# FPGA_SLM.net
KiCad netlist of a schematic drawn in Altium Designer
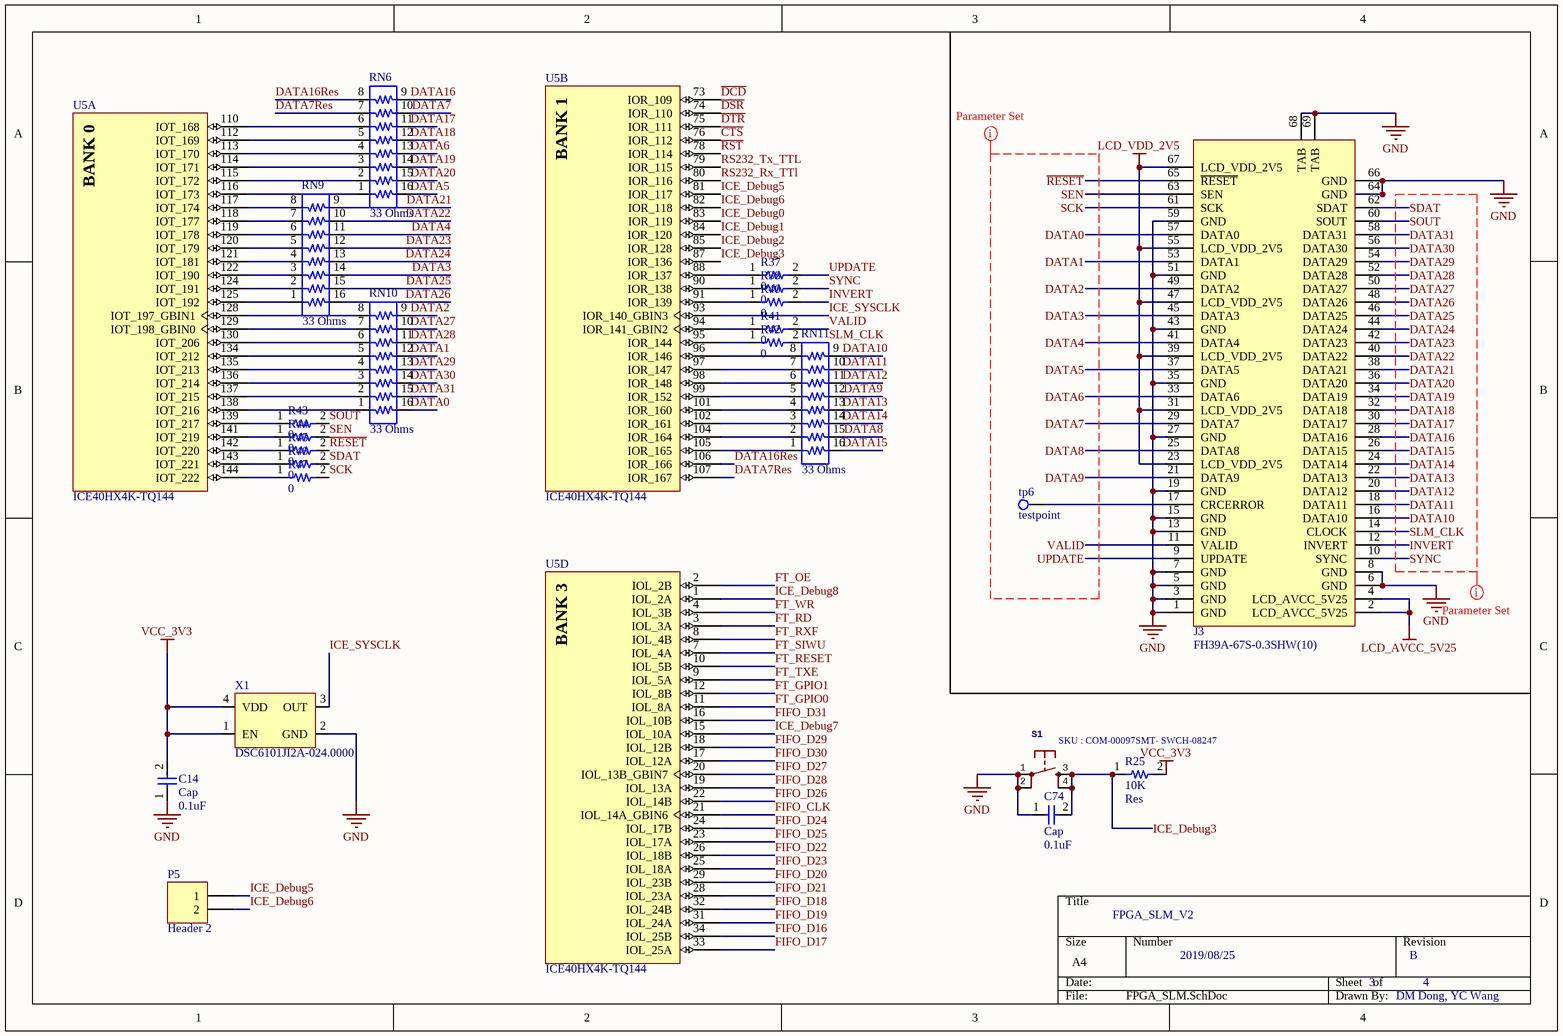
[diagram p0: FPGA_SLM.SchDoc]

(export (version "E")
  (design (tool "Eeschema 10.0.6"))
  (components
    (comp (ref "C14")
      (value "0.1uF")
      (footprint "Cap_0.1uF")
      (description "Multilayer Ceramic Capacitors MLCC - SMD/SMT 0.1uF 10% 50V AEC-Q200")
      (fields
        (field (name "COMPONENT NAME") "Cap")
        (field (name "Comment") "AC0603KRX7R9BB104")
        (field (name "CREATED BY") "Daoming Dong")
      )
      (libsource (lib "USB_FPGA_SLM_v1") (part "Cap_0.1uF"))
    )
    (comp (ref "C74")
      (value "0.1uF")
      (footprint "Cap_0.1uF")
      (description "Multilayer Ceramic Capacitors MLCC - SMD/SMT 0.1uF 10% 50V AEC-Q200")
      (fields
        (field (name "COMPONENT NAME") "Cap")
        (field (name "Comment") "AC0603KRX7R9BB104")
        (field (name "CREATED BY") "Daoming Dong")
      )
      (libsource (lib "USB_FPGA_SLM_v1") (part "Cap_0.1uF"))
    )
    (comp (ref "J3")
      (value "FH39A-67S-0.3SHW(10)")
      (footprint "Hirose_connector")
      (description "FFC & FPC Connectors FPC ZIF CONN 67 POS SMT HORZ MNT")
      (fields (field (name "CREATED BY") "Daoming Dong"))
      (libsource (lib "USB_FPGA_SLM_v1") (part "FH39A-67S-0.3SHW(10)"))
    )
    (comp (ref "P5")
      (value "Header 2")
      (footprint "HDR1X2")
      (description "Header, 2-Pin")
      (fields (field (name "PUBLISHER") "Altium Limited"))
      (libsource (lib "Miscellaneous Connectors") (part "Header 2"))
    )
    (comp (ref "R25")
      (value "10K")
      (footprint "RES_10K")
      (description "Thin Film Resistors - SMD 10K ohm 0.05% 50 ppm High-Precision")
      (fields
        (field (name "COMPONENT NAME") "Res")
        (field (name "Comment") "RT0603WRE0710KL")
        (field (name "CREATED BY") "Daoming Dong")
      )
      (libsource (lib "USB_FPGA_SLM_v1") (part "Res_10K"))
    )
    (comp (ref "R37")
      (value "0")
      (footprint "RES_0")
      (description "Thick Film Resistors - SMD 1/10Watt 0ohms Commercial Use")
      (fields (field (name "Comment") "CRCW06030000Z0EAC") (field (name "CREATED BY") "Daoming Dong"))
      (libsource (lib "USB_FPGA_SLM_v1") (part "Res_0"))
    )
    (comp (ref "R38")
      (value "0")
      (footprint "RES_0")
      (description "Thick Film Resistors - SMD 1/10Watt 0ohms Commercial Use")
      (fields (field (name "Comment") "CRCW06030000Z0EAC") (field (name "CREATED BY") "Daoming Dong"))
      (libsource (lib "USB_FPGA_SLM_v1") (part "Res_0"))
    )
    (comp (ref "R40")
      (value "0")
      (footprint "RES_0")
      (description "Thick Film Resistors - SMD 1/10Watt 0ohms Commercial Use")
      (fields (field (name "Comment") "CRCW06030000Z0EAC") (field (name "CREATED BY") "Daoming Dong"))
      (libsource (lib "USB_FPGA_SLM_v1") (part "Res_0"))
    )
    (comp (ref "R41")
      (value "0")
      (footprint "RES_0")
      (description "Thick Film Resistors - SMD 1/10Watt 0ohms Commercial Use")
      (fields (field (name "Comment") "CRCW06030000Z0EAC") (field (name "CREATED BY") "Daoming Dong"))
      (libsource (lib "USB_FPGA_SLM_v1") (part "Res_0"))
    )
    (comp (ref "R42")
      (value "0")
      (footprint "RES_0")
      (description "Thick Film Resistors - SMD 1/10Watt 0ohms Commercial Use")
      (fields (field (name "Comment") "CRCW06030000Z0EAC") (field (name "CREATED BY") "Daoming Dong"))
      (libsource (lib "USB_FPGA_SLM_v1") (part "Res_0"))
    )
    (comp (ref "R43")
      (value "0")
      (footprint "RES_0")
      (description "Thick Film Resistors - SMD 1/10Watt 0ohms Commercial Use")
      (fields (field (name "Comment") "CRCW06030000Z0EAC") (field (name "CREATED BY") "Daoming Dong"))
      (libsource (lib "USB_FPGA_SLM_v1") (part "Res_0"))
    )
    (comp (ref "R44")
      (value "0")
      (footprint "RES_0")
      (description "Thick Film Resistors - SMD 1/10Watt 0ohms Commercial Use")
      (fields (field (name "Comment") "CRCW06030000Z0EAC") (field (name "CREATED BY") "Daoming Dong"))
      (libsource (lib "USB_FPGA_SLM_v1") (part "Res_0"))
    )
    (comp (ref "R45")
      (value "0")
      (footprint "RES_0")
      (description "Thick Film Resistors - SMD 1/10Watt 0ohms Commercial Use")
      (fields (field (name "Comment") "CRCW06030000Z0EAC") (field (name "CREATED BY") "Daoming Dong"))
      (libsource (lib "USB_FPGA_SLM_v1") (part "Res_0"))
    )
    (comp (ref "R46")
      (value "0")
      (footprint "RES_0")
      (description "Thick Film Resistors - SMD 1/10Watt 0ohms Commercial Use")
      (fields (field (name "Comment") "CRCW06030000Z0EAC") (field (name "CREATED BY") "Daoming Dong"))
      (libsource (lib "USB_FPGA_SLM_v1") (part "Res_0"))
    )
    (comp (ref "R47")
      (value "0")
      (footprint "RES_0")
      (description "Thick Film Resistors - SMD 1/10Watt 0ohms Commercial Use")
      (fields (field (name "Comment") "CRCW06030000Z0EAC") (field (name "CREATED BY") "Daoming Dong"))
      (libsource (lib "USB_FPGA_SLM_v1") (part "Res_0"))
    )
    (comp (ref "RN6")
      (value "33 Ohms")
      (footprint "ResArray_0")
      (description "Resistor Networks & Arrays 33 OHM 5%")
      (fields (field (name "Comment") "EXB-2HV330JV"))
      (libsource (lib "USB_FPGA_SLM_v1") (part "ResArray"))
    )
    (comp (ref "RN9")
      (value "33 Ohms")
      (footprint "ResArray_0")
      (description "Resistor Networks & Arrays 33 OHM 5%")
      (fields (field (name "Comment") "EXB-2HV330JV"))
      (libsource (lib "USB_FPGA_SLM_v1") (part "ResArray"))
    )
    (comp (ref "RN10")
      (value "33 Ohms")
      (footprint "ResArray_0")
      (description "Resistor Networks & Arrays 33 OHM 5%")
      (fields (field (name "Comment") "EXB-2HV330JV"))
      (libsource (lib "USB_FPGA_SLM_v1") (part "ResArray"))
    )
    (comp (ref "RN11")
      (value "33 Ohms")
      (footprint "ResArray_0")
      (description "Resistor Networks & Arrays 33 OHM 5%")
      (fields (field (name "Comment") "EXB-2HV330JV"))
      (libsource (lib "USB_FPGA_SLM_v1") (part "ResArray"))
    )
    (comp (ref "S1")
      (value "SKU : COM-00097SMT- SWCH-08247")
      (footprint "TACTILE-PTH")
      (libsource (lib "SparkFun-Electromechanical") (part "TAC_SWITCHPTH"))
    )
    (comp (ref "tp6")
      (value "testpoint")
      (footprint "testpoint")
      (description "Testpoint for testing voltage")
      (fields (field (name "CREATED BY") "Daoming Dong"))
      (libsource (lib "USB_FPGA_SLM_v1") (part "Testpoint"))
    )
    (comp (ref "U5")
      (value "ICE40HX4K-TQ144")
      (footprint "LATC-TQFP-144_L")
      (fields (field (name "MANUFACTURER") "Lattice Semiconductor"))
      (libsource (lib "Lattice iCE40") (part "ICE40HX4K-TQ144"))
    )
    (comp (ref "X1")
      (value "DSC6101JI2A-024.0000")
      (footprint "24MHzOscillator")
      (description "Standard Clock Oscillators MEMS Oscillator, Ultra Low Power, LVCMOS, -40C-85C, 25ppm, 2.5x2.0mm")
      (fields (field (name "CREATED BY") "Daoming Dong"))
      (libsource (lib "USB_FPGA_SLM_v1") (part "24MHzOscillator"))
    )
  )
  (nets
    (net (code "1") (name "/DATA0") (class "Default")
      (node (ref "J3") (pin "57") (pinfunction "DATA0_57") (pintype "passive"))
      (node (ref "RN10") (pin "16") (pinfunction "16_16") (pintype "passive"))
    )
    (net (code "2") (name "/DATA1") (class "Default")
      (node (ref "J3") (pin "53") (pinfunction "DATA1_53") (pintype "passive"))
      (node (ref "RN10") (pin "12") (pinfunction "12_12") (pintype "passive"))
    )
    (net (code "3") (name "/DATA2") (class "Default")
      (node (ref "J3") (pin "49") (pinfunction "DATA2_49") (pintype "passive"))
      (node (ref "RN10") (pin "9") (pinfunction "9_9") (pintype "passive"))
    )
    (net (code "4") (name "/DATA3") (class "Default")
      (node (ref "J3") (pin "45") (pinfunction "DATA3_45") (pintype "passive"))
      (node (ref "RN9") (pin "14") (pinfunction "14_14") (pintype "passive"))
    )
    (net (code "5") (name "/DATA4") (class "Default")
      (node (ref "J3") (pin "41") (pinfunction "DATA4_41") (pintype "passive"))
      (node (ref "RN9") (pin "11") (pinfunction "11_11") (pintype "passive"))
    )
    (net (code "6") (name "/DATA5") (class "Default")
      (node (ref "J3") (pin "37") (pinfunction "DATA5_37") (pintype "passive"))
      (node (ref "RN6") (pin "16") (pinfunction "16_16") (pintype "passive"))
    )
    (net (code "7") (name "/DATA6") (class "Default")
      (node (ref "J3") (pin "33") (pinfunction "DATA6_33") (pintype "passive"))
      (node (ref "RN6") (pin "13") (pinfunction "13_13") (pintype "passive"))
    )
    (net (code "8") (name "/DATA7") (class "Default")
      (node (ref "J3") (pin "29") (pinfunction "DATA7_29") (pintype "passive"))
      (node (ref "RN6") (pin "10") (pinfunction "10_10") (pintype "passive"))
    )
    (net (code "9") (name "/DATA7Res") (class "Default")
      (node (ref "RN6") (pin "7") (pinfunction "7_7") (pintype "passive"))
      (node (ref "U5") (pin "107") (pinfunction "IOR_167_107") (pintype "bidirectional"))
    )
    (net (code "10") (name "/DATA8") (class "Default")
      (node (ref "J3") (pin "25") (pinfunction "DATA8_25") (pintype "passive"))
      (node (ref "RN11") (pin "15") (pinfunction "15_15") (pintype "passive"))
    )
    (net (code "11") (name "/DATA9") (class "Default")
      (node (ref "J3") (pin "21") (pinfunction "DATA9_21") (pintype "passive"))
      (node (ref "RN11") (pin "12") (pinfunction "12_12") (pintype "passive"))
    )
    (net (code "12") (name "/DATA10") (class "Default")
      (node (ref "J3") (pin "16") (pinfunction "DATA10_16") (pintype "passive"))
      (node (ref "RN11") (pin "9") (pinfunction "9_9") (pintype "passive"))
    )
    (net (code "13") (name "/DATA11") (class "Default")
      (node (ref "J3") (pin "18") (pinfunction "DATA11_18") (pintype "passive"))
      (node (ref "RN11") (pin "10") (pinfunction "10_10") (pintype "passive"))
    )
    (net (code "14") (name "/DATA12") (class "Default")
      (node (ref "J3") (pin "20") (pinfunction "DATA12_20") (pintype "passive"))
      (node (ref "RN11") (pin "11") (pinfunction "11_11") (pintype "passive"))
    )
    (net (code "15") (name "/DATA13") (class "Default")
      (node (ref "J3") (pin "22") (pinfunction "DATA13_22") (pintype "passive"))
      (node (ref "RN11") (pin "13") (pinfunction "13_13") (pintype "passive"))
    )
    (net (code "16") (name "/DATA14") (class "Default")
      (node (ref "J3") (pin "24") (pinfunction "DATA14_24") (pintype "passive"))
      (node (ref "RN11") (pin "14") (pinfunction "14_14") (pintype "passive"))
    )
    (net (code "17") (name "/DATA15") (class "Default")
      (node (ref "J3") (pin "26") (pinfunction "DATA15_26") (pintype "passive"))
      (node (ref "RN11") (pin "16") (pinfunction "16_16") (pintype "passive"))
    )
    (net (code "18") (name "/DATA16") (class "Default")
      (node (ref "J3") (pin "28") (pinfunction "DATA16_28") (pintype "passive"))
      (node (ref "RN6") (pin "9") (pinfunction "9_9") (pintype "passive"))
    )
    (net (code "19") (name "/DATA16Res") (class "Default")
      (node (ref "RN6") (pin "8") (pinfunction "8_8") (pintype "passive"))
      (node (ref "U5") (pin "106") (pinfunction "IOR_166_106") (pintype "bidirectional"))
    )
    (net (code "20") (name "/DATA17") (class "Default")
      (node (ref "J3") (pin "30") (pinfunction "DATA17_30") (pintype "passive"))
      (node (ref "RN6") (pin "11") (pinfunction "11_11") (pintype "passive"))
    )
    (net (code "21") (name "/DATA18") (class "Default")
      (node (ref "J3") (pin "32") (pinfunction "DATA18_32") (pintype "passive"))
      (node (ref "RN6") (pin "12") (pinfunction "12_12") (pintype "passive"))
    )
    (net (code "22") (name "/DATA19") (class "Default")
      (node (ref "J3") (pin "34") (pinfunction "DATA19_34") (pintype "passive"))
      (node (ref "RN6") (pin "14") (pinfunction "14_14") (pintype "passive"))
    )
    (net (code "23") (name "/DATA20") (class "Default")
      (node (ref "J3") (pin "36") (pinfunction "DATA20_36") (pintype "passive"))
      (node (ref "RN6") (pin "15") (pinfunction "15_15") (pintype "passive"))
    )
    (net (code "24") (name "/DATA21") (class "Default")
      (node (ref "J3") (pin "38") (pinfunction "DATA21_38") (pintype "passive"))
      (node (ref "RN9") (pin "9") (pinfunction "9_9") (pintype "passive"))
    )
    (net (code "25") (name "/DATA22") (class "Default")
      (node (ref "J3") (pin "40") (pinfunction "DATA22_40") (pintype "passive"))
      (node (ref "RN9") (pin "10") (pinfunction "10_10") (pintype "passive"))
    )
    (net (code "26") (name "/DATA23") (class "Default")
      (node (ref "J3") (pin "42") (pinfunction "DATA23_42") (pintype "passive"))
      (node (ref "RN9") (pin "12") (pinfunction "12_12") (pintype "passive"))
    )
    (net (code "27") (name "/DATA24") (class "Default")
      (node (ref "J3") (pin "44") (pinfunction "DATA24_44") (pintype "passive"))
      (node (ref "RN9") (pin "13") (pinfunction "13_13") (pintype "passive"))
    )
    (net (code "28") (name "/DATA25") (class "Default")
      (node (ref "J3") (pin "46") (pinfunction "DATA25_46") (pintype "passive"))
      (node (ref "RN9") (pin "15") (pinfunction "15_15") (pintype "passive"))
    )
    (net (code "29") (name "/DATA26") (class "Default")
      (node (ref "J3") (pin "48") (pinfunction "DATA26_48") (pintype "passive"))
      (node (ref "RN9") (pin "16") (pinfunction "16_16") (pintype "passive"))
    )
    (net (code "30") (name "/DATA27") (class "Default")
      (node (ref "J3") (pin "50") (pinfunction "DATA27_50") (pintype "passive"))
      (node (ref "RN10") (pin "10") (pinfunction "10_10") (pintype "passive"))
    )
    (net (code "31") (name "/DATA28") (class "Default")
      (node (ref "J3") (pin "52") (pinfunction "DATA28_52") (pintype "passive"))
      (node (ref "RN10") (pin "11") (pinfunction "11_11") (pintype "passive"))
    )
    (net (code "32") (name "/DATA29") (class "Default")
      (node (ref "J3") (pin "54") (pinfunction "DATA29_54") (pintype "passive"))
      (node (ref "RN10") (pin "13") (pinfunction "13_13") (pintype "passive"))
    )
    (net (code "33") (name "/DATA30") (class "Default")
      (node (ref "J3") (pin "56") (pinfunction "DATA30_56") (pintype "passive"))
      (node (ref "RN10") (pin "14") (pinfunction "14_14") (pintype "passive"))
    )
    (net (code "34") (name "/DATA31") (class "Default")
      (node (ref "J3") (pin "58") (pinfunction "DATA31_58") (pintype "passive"))
      (node (ref "RN10") (pin "15") (pinfunction "15_15") (pintype "passive"))
    )
    (net (code "35") (name "/FIFO_CLK") (class "Default")
      (node (ref "U5") (pin "21") (pinfunction "IOL_14A_GBIN6_21") (pintype "bidirectional"))
    )
    (net (code "36") (name "/FIFO_D16") (class "Default")
      (node (ref "U5") (pin "34") (pinfunction "IOL_25B_34") (pintype "bidirectional"))
    )
    (net (code "37") (name "/FIFO_D17") (class "Default")
      (node (ref "U5") (pin "33") (pinfunction "IOL_25A_33") (pintype "bidirectional"))
    )
    (net (code "38") (name "/FIFO_D18") (class "Default")
      (node (ref "U5") (pin "32") (pinfunction "IOL_24B_32") (pintype "bidirectional"))
    )
    (net (code "39") (name "/FIFO_D19") (class "Default")
      (node (ref "U5") (pin "31") (pinfunction "IOL_24A_31") (pintype "bidirectional"))
    )
    (net (code "40") (name "/FIFO_D20") (class "Default")
      (node (ref "U5") (pin "29") (pinfunction "IOL_23B_29") (pintype "bidirectional"))
    )
    (net (code "41") (name "/FIFO_D21") (class "Default")
      (node (ref "U5") (pin "28") (pinfunction "IOL_23A_28") (pintype "bidirectional"))
    )
    (net (code "42") (name "/FIFO_D22") (class "Default")
      (node (ref "U5") (pin "26") (pinfunction "IOL_18B_26") (pintype "bidirectional"))
    )
    (net (code "43") (name "/FIFO_D23") (class "Default")
      (node (ref "U5") (pin "25") (pinfunction "IOL_18A_25") (pintype "bidirectional"))
    )
    (net (code "44") (name "/FIFO_D24") (class "Default")
      (node (ref "U5") (pin "24") (pinfunction "IOL_17B_24") (pintype "bidirectional"))
    )
    (net (code "45") (name "/FIFO_D25") (class "Default")
      (node (ref "U5") (pin "23") (pinfunction "IOL_17A_23") (pintype "bidirectional"))
    )
    (net (code "46") (name "/FIFO_D26") (class "Default")
      (node (ref "U5") (pin "22") (pinfunction "IOL_14B_22") (pintype "bidirectional"))
    )
    (net (code "47") (name "/FIFO_D27") (class "Default")
      (node (ref "U5") (pin "20") (pinfunction "IOL_13B_GBIN7_20") (pintype "bidirectional"))
    )
    (net (code "48") (name "/FIFO_D28") (class "Default")
      (node (ref "U5") (pin "19") (pinfunction "IOL_13A_19") (pintype "bidirectional"))
    )
    (net (code "49") (name "/FIFO_D29") (class "Default")
      (node (ref "U5") (pin "18") (pinfunction "IOL_12B_18") (pintype "bidirectional"))
    )
    (net (code "50") (name "/FIFO_D30") (class "Default")
      (node (ref "U5") (pin "17") (pinfunction "IOL_12A_17") (pintype "bidirectional"))
    )
    (net (code "51") (name "/FIFO_D31") (class "Default")
      (node (ref "U5") (pin "16") (pinfunction "IOL_10B_16") (pintype "bidirectional"))
    )
    (net (code "52") (name "/FT_GPIO0") (class "Default")
      (node (ref "U5") (pin "11") (pinfunction "IOL_8A_11") (pintype "bidirectional"))
    )
    (net (code "53") (name "/FT_GPIO1") (class "Default")
      (node (ref "U5") (pin "12") (pinfunction "IOL_8B_12") (pintype "bidirectional"))
    )
    (net (code "54") (name "/FT_OE") (class "Default")
      (node (ref "U5") (pin "2") (pinfunction "IOL_2B_2") (pintype "bidirectional"))
    )
    (net (code "55") (name "/FT_RD") (class "Default")
      (node (ref "U5") (pin "3") (pinfunction "IOL_3A_3") (pintype "bidirectional"))
    )
    (net (code "56") (name "/FT_RESET") (class "Default")
      (node (ref "U5") (pin "10") (pinfunction "IOL_5B_10") (pintype "bidirectional"))
    )
    (net (code "57") (name "/FT_RXF") (class "Default")
      (node (ref "U5") (pin "8") (pinfunction "IOL_4B_8") (pintype "bidirectional"))
    )
    (net (code "58") (name "/FT_SIWU") (class "Default")
      (node (ref "U5") (pin "7") (pinfunction "IOL_4A_7") (pintype "bidirectional"))
    )
    (net (code "59") (name "/FT_TXE") (class "Default")
      (node (ref "U5") (pin "9") (pinfunction "IOL_5A_9") (pintype "bidirectional"))
    )
    (net (code "60") (name "/FT_WR") (class "Default")
      (node (ref "U5") (pin "4") (pinfunction "IOL_3B_4") (pintype "bidirectional"))
    )
    (net (code "61") (name "/ICE_Debug0") (class "Default")
      (node (ref "U5") (pin "83") (pinfunction "IOR_119_83") (pintype "bidirectional"))
    )
    (net (code "62") (name "/ICE_Debug1") (class "Default")
      (node (ref "U5") (pin "84") (pinfunction "IOR_120_84") (pintype "bidirectional"))
    )
    (net (code "63") (name "/ICE_Debug2") (class "Default")
      (node (ref "U5") (pin "85") (pinfunction "IOR_128_85") (pintype "bidirectional"))
    )
    (net (code "64") (name "/ICE_Debug3") (class "Default")
      (node (ref "C74") (pin "2") (pinfunction "2_2") (pintype "passive"))
      (node (ref "R25") (pin "1") (pinfunction "1_1") (pintype "passive"))
      (node (ref "S1") (pin "3") (pinfunction "3_3") (pintype "passive"))
      (node (ref "S1") (pin "4") (pinfunction "4_4") (pintype "passive"))
      (node (ref "U5") (pin "87") (pinfunction "IOR_136_87") (pintype "bidirectional"))
    )
    (net (code "65") (name "/ICE_Debug5") (class "Default")
      (node (ref "P5") (pin "1") (pinfunction "1_1") (pintype "passive"))
      (node (ref "U5") (pin "81") (pinfunction "IOR_117_81") (pintype "bidirectional"))
    )
    (net (code "66") (name "/ICE_Debug6") (class "Default")
      (node (ref "P5") (pin "2") (pinfunction "2_2") (pintype "passive"))
      (node (ref "U5") (pin "82") (pinfunction "IOR_118_82") (pintype "bidirectional"))
    )
    (net (code "67") (name "/ICE_Debug7") (class "Default")
      (node (ref "U5") (pin "15") (pinfunction "IOL_10A_15") (pintype "bidirectional"))
    )
    (net (code "68") (name "/ICE_Debug8") (class "Default")
      (node (ref "U5") (pin "1") (pinfunction "IOL_2A_1") (pintype "bidirectional"))
    )
    (net (code "69") (name "/ICE_SYSCLK") (class "Default")
      (node (ref "U5") (pin "93") (pinfunction "IOR_140_GBIN3_93") (pintype "bidirectional"))
      (node (ref "X1") (pin "3") (pinfunction "OUT_3") (pintype "passive"))
    )
    (net (code "70") (name "/INVERT") (class "Default")
      (node (ref "J3") (pin "12") (pinfunction "INVERT_12") (pintype "passive"))
      (node (ref "R40") (pin "2") (pinfunction "2_2") (pintype "passive"))
    )
    (net (code "71") (name "/RS232_Rx_TTl") (class "Default")
      (node (ref "U5") (pin "80") (pinfunction "IOR_116_80") (pintype "bidirectional"))
    )
    (net (code "72") (name "/RS232_Tx_TTL") (class "Default")
      (node (ref "U5") (pin "79") (pinfunction "IOR_115_79") (pintype "bidirectional"))
    )
    (net (code "73") (name "/SCK") (class "Default")
      (node (ref "J3") (pin "61") (pinfunction "SCK_61") (pintype "passive"))
      (node (ref "R47") (pin "2") (pinfunction "2_2") (pintype "passive"))
    )
    (net (code "74") (name "/SDAT") (class "Default")
      (node (ref "J3") (pin "62") (pinfunction "SDAT_62") (pintype "passive"))
      (node (ref "R46") (pin "2") (pinfunction "2_2") (pintype "passive"))
    )
    (net (code "75") (name "/SEN") (class "Default")
      (node (ref "J3") (pin "63") (pinfunction "SEN_63") (pintype "passive"))
      (node (ref "R44") (pin "2") (pinfunction "2_2") (pintype "passive"))
    )
    (net (code "76") (name "/SLM_CLK") (class "Default")
      (node (ref "J3") (pin "14") (pinfunction "CLOCK_14") (pintype "passive"))
      (node (ref "R42") (pin "2") (pinfunction "2_2") (pintype "passive"))
    )
    (net (code "77") (name "/SOUT") (class "Default")
      (node (ref "J3") (pin "60") (pinfunction "SOUT_60") (pintype "passive"))
      (node (ref "R43") (pin "2") (pinfunction "2_2") (pintype "passive"))
    )
    (net (code "78") (name "/SYNC") (class "Default")
      (node (ref "J3") (pin "10") (pinfunction "SYNC_10") (pintype "passive"))
      (node (ref "R38") (pin "2") (pinfunction "2_2") (pintype "passive"))
    )
    (net (code "79") (name "/UPDATE") (class "Default")
      (node (ref "J3") (pin "9") (pinfunction "UPDATE_9") (pintype "passive"))
      (node (ref "R37") (pin "2") (pinfunction "2_2") (pintype "passive"))
    )
    (net (code "80") (name "/VALID") (class "Default")
      (node (ref "J3") (pin "11") (pinfunction "VALID_11") (pintype "passive"))
      (node (ref "R41") (pin "2") (pinfunction "2_2") (pintype "passive"))
    )
    (net (code "81") (name "/~{CTS}") (class "Default")
      (node (ref "U5") (pin "76") (pinfunction "IOR_112_76") (pintype "bidirectional"))
    )
    (net (code "82") (name "/~{DCD}") (class "Default")
      (node (ref "U5") (pin "73") (pinfunction "IOR_109_73") (pintype "bidirectional"))
    )
    (net (code "83") (name "/~{DSR}") (class "Default")
      (node (ref "U5") (pin "74") (pinfunction "IOR_110_74") (pintype "bidirectional"))
    )
    (net (code "84") (name "/~{DTR}") (class "Default")
      (node (ref "U5") (pin "75") (pinfunction "IOR_111_75") (pintype "bidirectional"))
    )
    (net (code "85") (name "/~{RESET}") (class "Default")
      (node (ref "J3") (pin "65") (pinfunction "~{RESET}_65") (pintype "passive"))
      (node (ref "R45") (pin "2") (pinfunction "2_2") (pintype "passive"))
    )
    (net (code "86") (name "/~{RST}") (class "Default")
      (node (ref "U5") (pin "78") (pinfunction "IOR_114_78") (pintype "bidirectional"))
    )
    (net (code "87") (name "GND") (class "Default")
      (node (ref "C14") (pin "1") (pinfunction "1_1") (pintype "passive"))
      (node (ref "C74") (pin "1") (pinfunction "1_1") (pintype "passive"))
      (node (ref "J3") (pin "1") (pinfunction "GND_1") (pintype "passive"))
      (node (ref "J3") (pin "13") (pinfunction "GND_13") (pintype "passive"))
      (node (ref "J3") (pin "15") (pinfunction "GND_15") (pintype "passive"))
      (node (ref "J3") (pin "19") (pinfunction "GND_19") (pintype "passive"))
      (node (ref "J3") (pin "27") (pinfunction "GND_27") (pintype "passive"))
      (node (ref "J3") (pin "3") (pinfunction "GND_3") (pintype "passive"))
      (node (ref "J3") (pin "35") (pinfunction "GND_35") (pintype "passive"))
      (node (ref "J3") (pin "43") (pinfunction "GND_43") (pintype "passive"))
      (node (ref "J3") (pin "5") (pinfunction "GND_5") (pintype "passive"))
      (node (ref "J3") (pin "51") (pinfunction "GND_51") (pintype "passive"))
      (node (ref "J3") (pin "59") (pinfunction "GND_59") (pintype "passive"))
      (node (ref "J3") (pin "6") (pinfunction "GND_6") (pintype "passive"))
      (node (ref "J3") (pin "64") (pinfunction "GND_64") (pintype "passive"))
      (node (ref "J3") (pin "66") (pinfunction "GND_66") (pintype "passive"))
      (node (ref "J3") (pin "68") (pinfunction "TAB_68") (pintype "passive"))
      (node (ref "J3") (pin "69") (pinfunction "TAB_69") (pintype "passive"))
      (node (ref "J3") (pin "7") (pinfunction "GND_7") (pintype "passive"))
      (node (ref "J3") (pin "8") (pinfunction "GND_8") (pintype "passive"))
      (node (ref "S1") (pin "1") (pinfunction "1_1") (pintype "passive"))
      (node (ref "S1") (pin "2") (pinfunction "2_2") (pintype "passive"))
      (node (ref "X1") (pin "2") (pinfunction "GND_2") (pintype "passive"))
    )
    (net (code "88") (name "LCD_AVCC_5V25") (class "Default")
      (node (ref "J3") (pin "2") (pinfunction "LCD_AVCC_5V25_2") (pintype "passive"))
      (node (ref "J3") (pin "4") (pinfunction "LCD_AVCC_5V25_4") (pintype "passive"))
    )
    (net (code "89") (name "LCD_VDD_2V5") (class "Default")
      (node (ref "J3") (pin "23") (pinfunction "LCD_VDD_2V5_23") (pintype "passive"))
      (node (ref "J3") (pin "31") (pinfunction "LCD_VDD_2V5_31") (pintype "passive"))
      (node (ref "J3") (pin "39") (pinfunction "LCD_VDD_2V5_39") (pintype "passive"))
      (node (ref "J3") (pin "47") (pinfunction "LCD_VDD_2V5_47") (pintype "passive"))
      (node (ref "J3") (pin "55") (pinfunction "LCD_VDD_2V5_55") (pintype "passive"))
      (node (ref "J3") (pin "67") (pinfunction "LCD_VDD_2V5_67") (pintype "passive"))
    )
    (net (code "90") (name "Net-(J3-CRCERROR)") (class "Default")
      (node (ref "J3") (pin "17") (pinfunction "CRCERROR_17") (pintype "passive"))
      (node (ref "tp6") (pin "1") (pinfunction "1_1") (pintype "passive"))
    )
    (net (code "91") (name "Net-(U5A-IOT_168)") (class "Default")
      (node (ref "RN6") (pin "6") (pinfunction "6_6") (pintype "passive"))
      (node (ref "U5") (pin "110") (pinfunction "IOT_168_110") (pintype "bidirectional"))
    )
    (net (code "92") (name "Net-(U5A-IOT_169)") (class "Default")
      (node (ref "RN6") (pin "5") (pinfunction "5_5") (pintype "passive"))
      (node (ref "U5") (pin "112") (pinfunction "IOT_169_112") (pintype "bidirectional"))
    )
    (net (code "93") (name "Net-(U5A-IOT_170)") (class "Default")
      (node (ref "RN6") (pin "4") (pinfunction "4_4") (pintype "passive"))
      (node (ref "U5") (pin "113") (pinfunction "IOT_170_113") (pintype "bidirectional"))
    )
    (net (code "94") (name "Net-(U5A-IOT_171)") (class "Default")
      (node (ref "RN6") (pin "3") (pinfunction "3_3") (pintype "passive"))
      (node (ref "U5") (pin "114") (pinfunction "IOT_171_114") (pintype "bidirectional"))
    )
    (net (code "95") (name "Net-(U5A-IOT_172)") (class "Default")
      (node (ref "RN6") (pin "2") (pinfunction "2_2") (pintype "passive"))
      (node (ref "U5") (pin "115") (pinfunction "IOT_172_115") (pintype "bidirectional"))
    )
    (net (code "96") (name "Net-(U5A-IOT_173)") (class "Default")
      (node (ref "RN6") (pin "1") (pinfunction "1_1") (pintype "passive"))
      (node (ref "U5") (pin "116") (pinfunction "IOT_173_116") (pintype "bidirectional"))
    )
    (net (code "97") (name "Net-(U5A-IOT_174)") (class "Default")
      (node (ref "RN9") (pin "8") (pinfunction "8_8") (pintype "passive"))
      (node (ref "U5") (pin "117") (pinfunction "IOT_174_117") (pintype "bidirectional"))
    )
    (net (code "98") (name "Net-(U5A-IOT_177)") (class "Default")
      (node (ref "RN9") (pin "7") (pinfunction "7_7") (pintype "passive"))
      (node (ref "U5") (pin "118") (pinfunction "IOT_177_118") (pintype "bidirectional"))
    )
    (net (code "99") (name "Net-(U5A-IOT_178)") (class "Default")
      (node (ref "RN9") (pin "6") (pinfunction "6_6") (pintype "passive"))
      (node (ref "U5") (pin "119") (pinfunction "IOT_178_119") (pintype "bidirectional"))
    )
    (net (code "100") (name "Net-(U5A-IOT_179)") (class "Default")
      (node (ref "RN9") (pin "5") (pinfunction "5_5") (pintype "passive"))
      (node (ref "U5") (pin "120") (pinfunction "IOT_179_120") (pintype "bidirectional"))
    )
    (net (code "101") (name "Net-(U5A-IOT_181)") (class "Default")
      (node (ref "RN9") (pin "4") (pinfunction "4_4") (pintype "passive"))
      (node (ref "U5") (pin "121") (pinfunction "IOT_181_121") (pintype "bidirectional"))
    )
    (net (code "102") (name "Net-(U5A-IOT_190)") (class "Default")
      (node (ref "RN9") (pin "3") (pinfunction "3_3") (pintype "passive"))
      (node (ref "U5") (pin "122") (pinfunction "IOT_190_122") (pintype "bidirectional"))
    )
    (net (code "103") (name "Net-(U5A-IOT_191)") (class "Default")
      (node (ref "RN9") (pin "2") (pinfunction "2_2") (pintype "passive"))
      (node (ref "U5") (pin "124") (pinfunction "IOT_191_124") (pintype "bidirectional"))
    )
    (net (code "104") (name "Net-(U5A-IOT_192)") (class "Default")
      (node (ref "RN9") (pin "1") (pinfunction "1_1") (pintype "passive"))
      (node (ref "U5") (pin "125") (pinfunction "IOT_192_125") (pintype "bidirectional"))
    )
    (net (code "105") (name "Net-(U5A-IOT_197_GBIN1)") (class "Default")
      (node (ref "RN10") (pin "8") (pinfunction "8_8") (pintype "passive"))
      (node (ref "U5") (pin "128") (pinfunction "IOT_197_GBIN1_128") (pintype "bidirectional"))
    )
    (net (code "106") (name "Net-(U5A-IOT_198_GBIN0)") (class "Default")
      (node (ref "RN10") (pin "7") (pinfunction "7_7") (pintype "passive"))
      (node (ref "U5") (pin "129") (pinfunction "IOT_198_GBIN0_129") (pintype "bidirectional"))
    )
    (net (code "107") (name "Net-(U5A-IOT_206)") (class "Default")
      (node (ref "RN10") (pin "6") (pinfunction "6_6") (pintype "passive"))
      (node (ref "U5") (pin "130") (pinfunction "IOT_206_130") (pintype "bidirectional"))
    )
    (net (code "108") (name "Net-(U5A-IOT_212)") (class "Default")
      (node (ref "RN10") (pin "5") (pinfunction "5_5") (pintype "passive"))
      (node (ref "U5") (pin "134") (pinfunction "IOT_212_134") (pintype "bidirectional"))
    )
    (net (code "109") (name "Net-(U5A-IOT_213)") (class "Default")
      (node (ref "RN10") (pin "4") (pinfunction "4_4") (pintype "passive"))
      (node (ref "U5") (pin "135") (pinfunction "IOT_213_135") (pintype "bidirectional"))
    )
    (net (code "110") (name "Net-(U5A-IOT_214)") (class "Default")
      (node (ref "RN10") (pin "3") (pinfunction "3_3") (pintype "passive"))
      (node (ref "U5") (pin "136") (pinfunction "IOT_214_136") (pintype "bidirectional"))
    )
    (net (code "111") (name "Net-(U5A-IOT_215)") (class "Default")
      (node (ref "RN10") (pin "2") (pinfunction "2_2") (pintype "passive"))
      (node (ref "U5") (pin "137") (pinfunction "IOT_215_137") (pintype "bidirectional"))
    )
    (net (code "112") (name "Net-(U5A-IOT_216)") (class "Default")
      (node (ref "RN10") (pin "1") (pinfunction "1_1") (pintype "passive"))
      (node (ref "U5") (pin "138") (pinfunction "IOT_216_138") (pintype "bidirectional"))
    )
    (net (code "113") (name "Net-(U5A-IOT_217)") (class "Default")
      (node (ref "R43") (pin "1") (pinfunction "1_1") (pintype "passive"))
      (node (ref "U5") (pin "139") (pinfunction "IOT_217_139") (pintype "bidirectional"))
    )
    (net (code "114") (name "Net-(U5A-IOT_219)") (class "Default")
      (node (ref "R44") (pin "1") (pinfunction "1_1") (pintype "passive"))
      (node (ref "U5") (pin "141") (pinfunction "IOT_219_141") (pintype "bidirectional"))
    )
    (net (code "115") (name "Net-(U5A-IOT_220)") (class "Default")
      (node (ref "R45") (pin "1") (pinfunction "1_1") (pintype "passive"))
      (node (ref "U5") (pin "142") (pinfunction "IOT_220_142") (pintype "bidirectional"))
    )
    (net (code "116") (name "Net-(U5A-IOT_221)") (class "Default")
      (node (ref "R46") (pin "1") (pinfunction "1_1") (pintype "passive"))
      (node (ref "U5") (pin "143") (pinfunction "IOT_221_143") (pintype "bidirectional"))
    )
    (net (code "117") (name "Net-(U5A-IOT_222)") (class "Default")
      (node (ref "R47") (pin "1") (pinfunction "1_1") (pintype "passive"))
      (node (ref "U5") (pin "144") (pinfunction "IOT_222_144") (pintype "bidirectional"))
    )
    (net (code "118") (name "Net-(U5B-IOR_137)") (class "Default")
      (node (ref "R37") (pin "1") (pinfunction "1_1") (pintype "passive"))
      (node (ref "U5") (pin "88") (pinfunction "IOR_137_88") (pintype "bidirectional"))
    )
    (net (code "119") (name "Net-(U5B-IOR_138)") (class "Default")
      (node (ref "R38") (pin "1") (pinfunction "1_1") (pintype "passive"))
      (node (ref "U5") (pin "90") (pinfunction "IOR_138_90") (pintype "bidirectional"))
    )
    (net (code "120") (name "Net-(U5B-IOR_139)") (class "Default")
      (node (ref "R40") (pin "1") (pinfunction "1_1") (pintype "passive"))
      (node (ref "U5") (pin "91") (pinfunction "IOR_139_91") (pintype "bidirectional"))
    )
    (net (code "121") (name "Net-(U5B-IOR_141_GBIN2)") (class "Default")
      (node (ref "R41") (pin "1") (pinfunction "1_1") (pintype "passive"))
      (node (ref "U5") (pin "94") (pinfunction "IOR_141_GBIN2_94") (pintype "bidirectional"))
    )
    (net (code "122") (name "Net-(U5B-IOR_144)") (class "Default")
      (node (ref "R42") (pin "1") (pinfunction "1_1") (pintype "passive"))
      (node (ref "U5") (pin "95") (pinfunction "IOR_144_95") (pintype "bidirectional"))
    )
    (net (code "123") (name "Net-(U5B-IOR_146)") (class "Default")
      (node (ref "RN11") (pin "8") (pinfunction "8_8") (pintype "passive"))
      (node (ref "U5") (pin "96") (pinfunction "IOR_146_96") (pintype "bidirectional"))
    )
    (net (code "124") (name "Net-(U5B-IOR_147)") (class "Default")
      (node (ref "RN11") (pin "7") (pinfunction "7_7") (pintype "passive"))
      (node (ref "U5") (pin "97") (pinfunction "IOR_147_97") (pintype "bidirectional"))
    )
    (net (code "125") (name "Net-(U5B-IOR_148)") (class "Default")
      (node (ref "RN11") (pin "6") (pinfunction "6_6") (pintype "passive"))
      (node (ref "U5") (pin "98") (pinfunction "IOR_148_98") (pintype "bidirectional"))
    )
    (net (code "126") (name "Net-(U5B-IOR_152)") (class "Default")
      (node (ref "RN11") (pin "5") (pinfunction "5_5") (pintype "passive"))
      (node (ref "U5") (pin "99") (pinfunction "IOR_152_99") (pintype "bidirectional"))
    )
    (net (code "127") (name "Net-(U5B-IOR_160)") (class "Default")
      (node (ref "RN11") (pin "4") (pinfunction "4_4") (pintype "passive"))
      (node (ref "U5") (pin "101") (pinfunction "IOR_160_101") (pintype "bidirectional"))
    )
    (net (code "128") (name "Net-(U5B-IOR_161)") (class "Default")
      (node (ref "RN11") (pin "3") (pinfunction "3_3") (pintype "passive"))
      (node (ref "U5") (pin "102") (pinfunction "IOR_161_102") (pintype "bidirectional"))
    )
    (net (code "129") (name "Net-(U5B-IOR_164)") (class "Default")
      (node (ref "RN11") (pin "2") (pinfunction "2_2") (pintype "passive"))
      (node (ref "U5") (pin "104") (pinfunction "IOR_164_104") (pintype "bidirectional"))
    )
    (net (code "130") (name "Net-(U5B-IOR_165)") (class "Default")
      (node (ref "RN11") (pin "1") (pinfunction "1_1") (pintype "passive"))
      (node (ref "U5") (pin "105") (pinfunction "IOR_165_105") (pintype "bidirectional"))
    )
    (net (code "131") (name "VCC_3V3") (class "Default")
      (node (ref "C14") (pin "2") (pinfunction "2_2") (pintype "passive"))
      (node (ref "R25") (pin "2") (pinfunction "2_2") (pintype "passive"))
      (node (ref "X1") (pin "1") (pinfunction "EN_1") (pintype "passive"))
      (node (ref "X1") (pin "4") (pinfunction "VDD_4") (pintype "passive"))
    )
  )
)
